# power.net
KiCad netlist of a schematic drawn in EAGLE
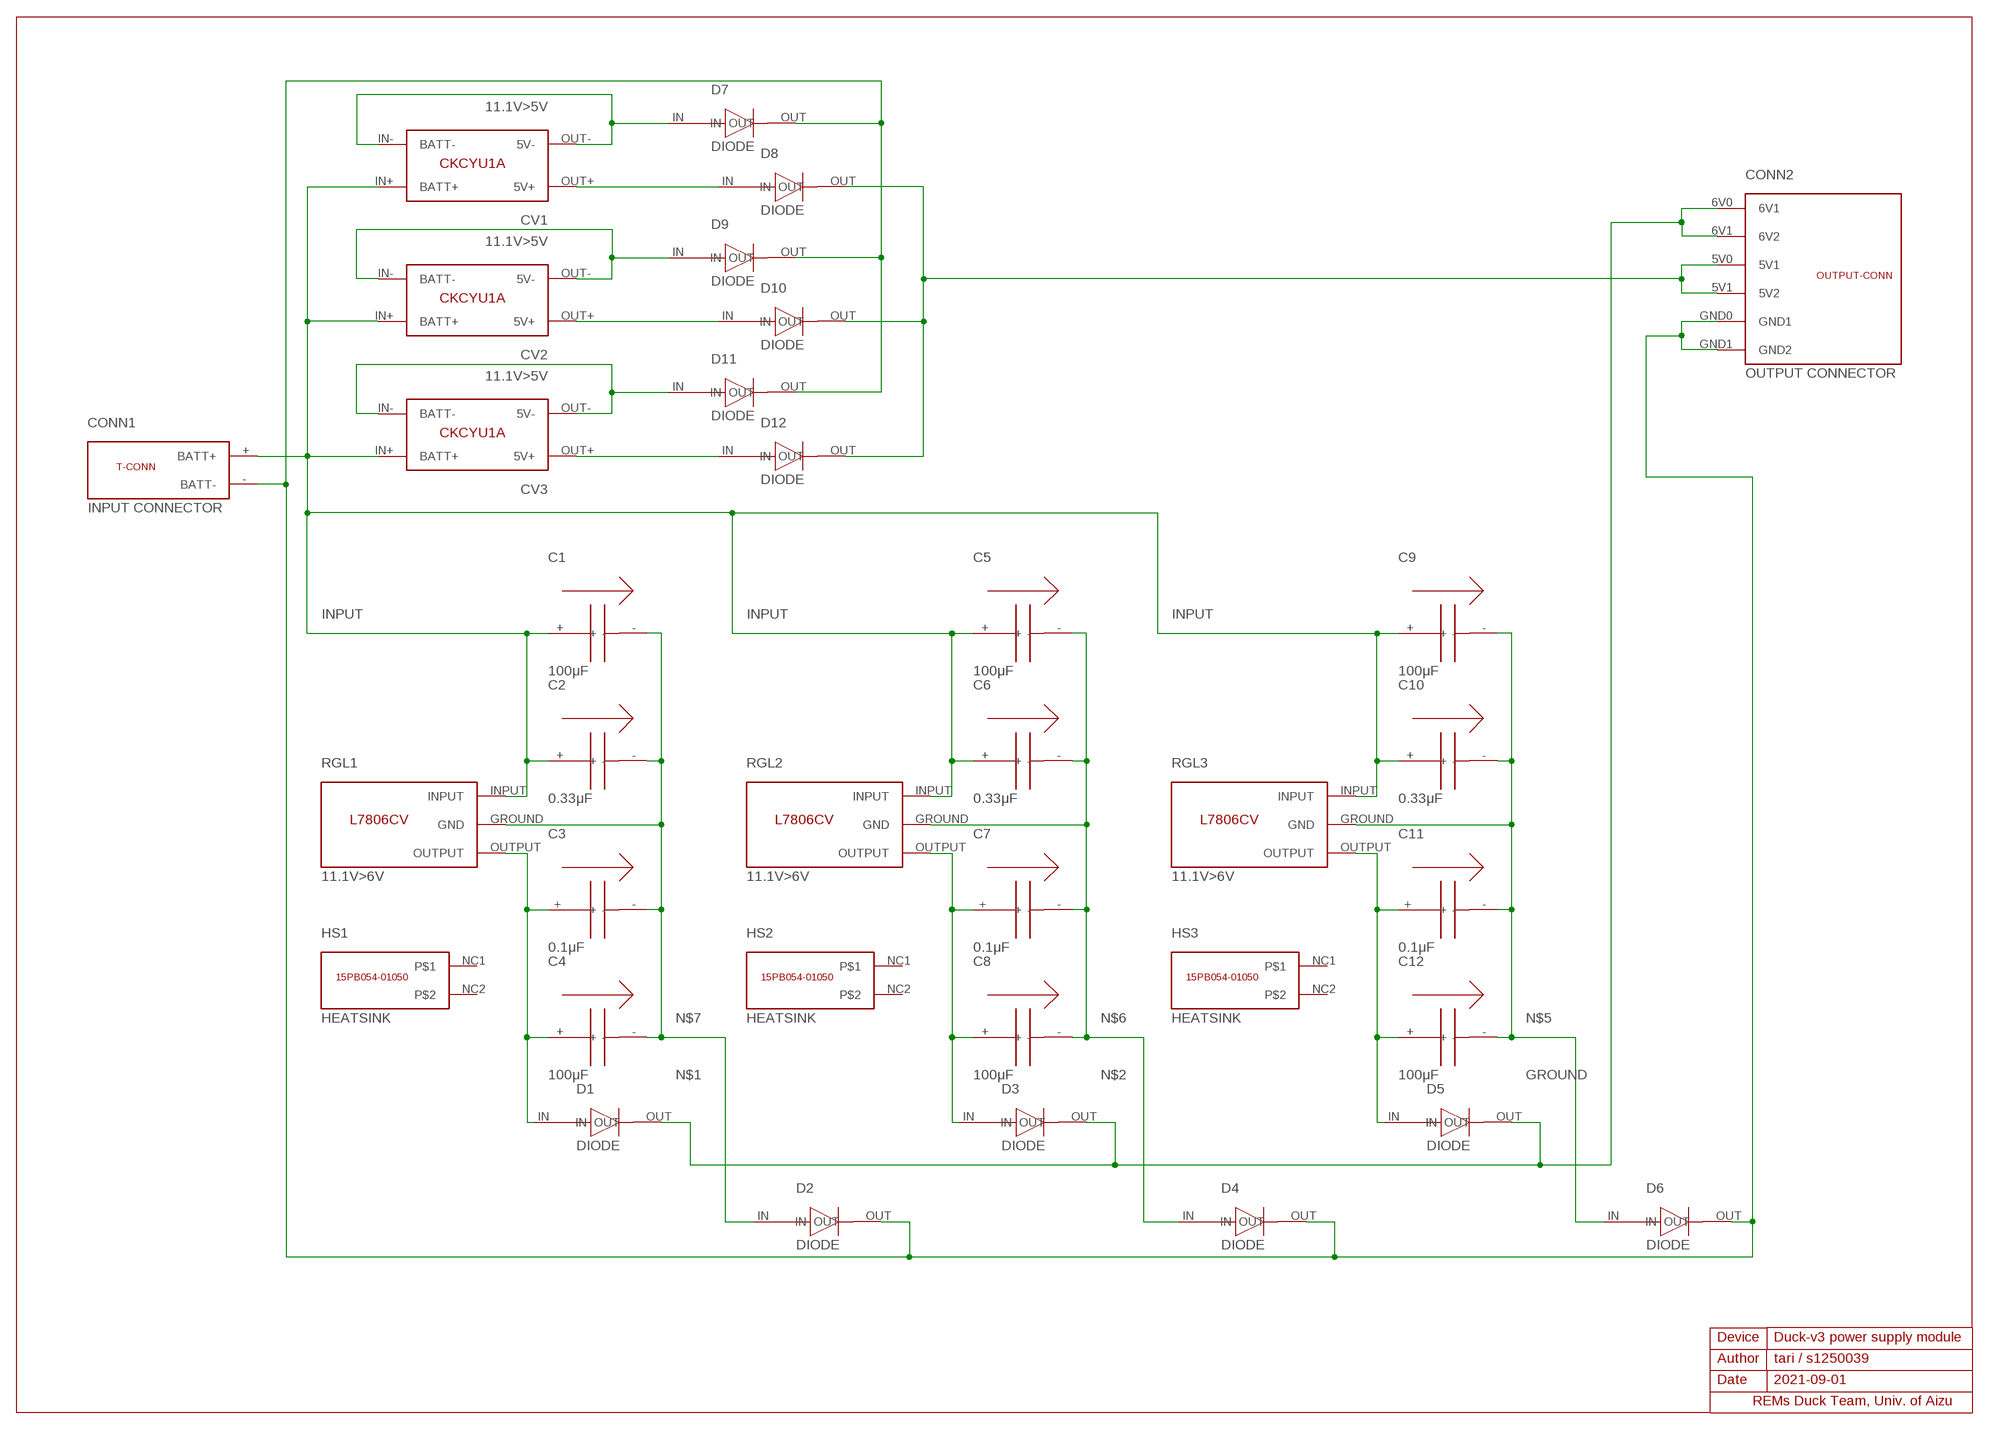
[diagram p0: schematic, sheet 1]

(export (version "E")
  (design (tool "Eeschema 10.0.6"))
  (components
    (comp (ref "C1")
      (value "100μF")
      (footprint "eagle-import:C-100μF")
      (libsource (lib "eagle-import") (part "C-100μF"))
    )
    (comp (ref "C2")
      (value "0.33μF")
      (footprint "eagle-import:C-0.33μF")
      (libsource (lib "eagle-import") (part "C-0.33μF"))
    )
    (comp (ref "C3")
      (value "0.1μF")
      (footprint "eagle-import:C-0.1μF")
      (libsource (lib "eagle-import") (part "C-0.1μF"))
    )
    (comp (ref "C4")
      (value "100μF")
      (footprint "eagle-import:C-100μF")
      (libsource (lib "eagle-import") (part "C-100μF"))
    )
    (comp (ref "C5")
      (value "100μF")
      (footprint "eagle-import:C-100μF")
      (libsource (lib "eagle-import") (part "C-100μF"))
    )
    (comp (ref "C6")
      (value "0.33μF")
      (footprint "eagle-import:C-0.33μF")
      (libsource (lib "eagle-import") (part "C-0.33μF"))
    )
    (comp (ref "C7")
      (value "0.1μF")
      (footprint "eagle-import:C-0.1μF")
      (libsource (lib "eagle-import") (part "C-0.1μF"))
    )
    (comp (ref "C8")
      (value "100μF")
      (footprint "eagle-import:C-100μF")
      (libsource (lib "eagle-import") (part "C-100μF"))
    )
    (comp (ref "C9")
      (value "100μF")
      (footprint "eagle-import:C-100μF")
      (libsource (lib "eagle-import") (part "C-100μF"))
    )
    (comp (ref "C10")
      (value "0.33μF")
      (footprint "eagle-import:C-0.33μF")
      (libsource (lib "eagle-import") (part "C-0.33μF"))
    )
    (comp (ref "C11")
      (value "0.1μF")
      (footprint "eagle-import:C-0.1μF")
      (libsource (lib "eagle-import") (part "C-0.1μF"))
    )
    (comp (ref "C12")
      (value "100μF")
      (footprint "eagle-import:C-100μF")
      (libsource (lib "eagle-import") (part "C-100μF"))
    )
    (comp (ref "CONN1")
      (value "INPUT CONNECTOR")
      (footprint "eagle-import:T-CONN")
      (libsource (lib "eagle-import") (part "T-CONN"))
    )
    (comp (ref "CONN2")
      (value "OUTPUT CONNECTOR")
      (footprint "eagle-import:OUTPUT-CONN")
      (libsource (lib "eagle-import") (part "OUTPUT-CONN"))
    )
    (comp (ref "CV1")
      (value "11.1V>5V")
      (footprint "eagle-import:CKCYU1A")
      (libsource (lib "eagle-import") (part "CKCYU1A"))
    )
    (comp (ref "CV2")
      (value "11.1V>5V")
      (footprint "eagle-import:CKCYU1A")
      (libsource (lib "eagle-import") (part "CKCYU1A"))
    )
    (comp (ref "CV3")
      (value "11.1V>5V")
      (footprint "eagle-import:CKCYU1A")
      (libsource (lib "eagle-import") (part "CKCYU1A"))
    )
    (comp (ref "D1")
      (value "DIODE")
      (footprint "eagle-import:DIODE")
      (libsource (lib "eagle-import") (part "DIODE"))
    )
    (comp (ref "D2")
      (value "DIODE")
      (footprint "eagle-import:DIODE")
      (libsource (lib "eagle-import") (part "DIODE"))
    )
    (comp (ref "D3")
      (value "DIODE")
      (footprint "eagle-import:DIODE")
      (libsource (lib "eagle-import") (part "DIODE"))
    )
    (comp (ref "D4")
      (value "DIODE")
      (footprint "eagle-import:DIODE")
      (libsource (lib "eagle-import") (part "DIODE"))
    )
    (comp (ref "D5")
      (value "DIODE")
      (footprint "eagle-import:DIODE")
      (libsource (lib "eagle-import") (part "DIODE"))
    )
    (comp (ref "D6")
      (value "DIODE")
      (footprint "eagle-import:DIODE")
      (libsource (lib "eagle-import") (part "DIODE"))
    )
    (comp (ref "D7")
      (value "DIODE")
      (footprint "eagle-import:DIODE")
      (libsource (lib "eagle-import") (part "DIODE"))
    )
    (comp (ref "D8")
      (value "DIODE")
      (footprint "eagle-import:DIODE")
      (libsource (lib "eagle-import") (part "DIODE"))
    )
    (comp (ref "D9")
      (value "DIODE")
      (footprint "eagle-import:DIODE")
      (libsource (lib "eagle-import") (part "DIODE"))
    )
    (comp (ref "D10")
      (value "DIODE")
      (footprint "eagle-import:DIODE")
      (libsource (lib "eagle-import") (part "DIODE"))
    )
    (comp (ref "D11")
      (value "DIODE")
      (footprint "eagle-import:DIODE")
      (libsource (lib "eagle-import") (part "DIODE"))
    )
    (comp (ref "D12")
      (value "DIODE")
      (footprint "eagle-import:DIODE")
      (libsource (lib "eagle-import") (part "DIODE"))
    )
    (comp (ref "HS1")
      (value "HEATSINK")
      (footprint "eagle-import:15PB054-01050")
      (libsource (lib "eagle-import") (part "15PB054-01050"))
    )
    (comp (ref "HS2")
      (value "HEATSINK")
      (footprint "eagle-import:15PB054-01050")
      (libsource (lib "eagle-import") (part "15PB054-01050"))
    )
    (comp (ref "HS3")
      (value "HEATSINK")
      (footprint "eagle-import:15PB054-01050")
      (libsource (lib "eagle-import") (part "15PB054-01050"))
    )
    (comp (ref "RGL1")
      (value "11.1V>6V")
      (footprint "eagle-import:L7806CV")
      (libsource (lib "eagle-import") (part "L7806CV"))
    )
    (comp (ref "RGL2")
      (value "11.1V>6V")
      (footprint "eagle-import:L7806CV")
      (libsource (lib "eagle-import") (part "L7806CV"))
    )
    (comp (ref "RGL3")
      (value "11.1V>6V")
      (footprint "eagle-import:L7806CV")
      (libsource (lib "eagle-import") (part "L7806CV"))
    )
  )
  (nets
    (net (code "1") (name "/GROUND") (class "Default")
      (node (ref "CONN1") (pin "-") (pinfunction "BATT-_-") (pintype "bidirectional"))
      (node (ref "CONN2") (pin "GND0") (pinfunction "GND1_GND0") (pintype "input"))
      (node (ref "CONN2") (pin "GND1") (pinfunction "GND2_GND1") (pintype "input"))
      (node (ref "D11") (pin "OUT") (pinfunction "OUT_OUT") (pintype "output"))
      (node (ref "D2") (pin "OUT") (pinfunction "OUT_OUT") (pintype "output"))
      (node (ref "D4") (pin "OUT") (pinfunction "OUT_OUT") (pintype "output"))
      (node (ref "D6") (pin "OUT") (pinfunction "OUT_OUT") (pintype "output"))
      (node (ref "D7") (pin "OUT") (pinfunction "OUT_OUT") (pintype "output"))
      (node (ref "D9") (pin "OUT") (pinfunction "OUT_OUT") (pintype "output"))
    )
    (net (code "2") (name "/INPUT") (class "Default")
      (node (ref "C1") (pin "+") (pinfunction "+_+") (pintype "input"))
      (node (ref "C10") (pin "+") (pinfunction "+_+") (pintype "input"))
      (node (ref "C2") (pin "+") (pinfunction "+_+") (pintype "input"))
      (node (ref "C5") (pin "+") (pinfunction "+_+") (pintype "input"))
      (node (ref "C6") (pin "+") (pinfunction "+_+") (pintype "input"))
      (node (ref "C9") (pin "+") (pinfunction "+_+") (pintype "input"))
      (node (ref "CONN1") (pin "+") (pinfunction "BATT+_+") (pintype "bidirectional"))
      (node (ref "CV1") (pin "IN+") (pinfunction "BATT+_IN+") (pintype "input"))
      (node (ref "CV2") (pin "IN+") (pinfunction "BATT+_IN+") (pintype "input"))
      (node (ref "CV3") (pin "IN+") (pinfunction "BATT+_IN+") (pintype "input"))
      (node (ref "RGL1") (pin "INPUT") (pinfunction "INPUT_INPUT") (pintype "input"))
      (node (ref "RGL2") (pin "INPUT") (pinfunction "INPUT_INPUT") (pintype "input"))
      (node (ref "RGL3") (pin "INPUT") (pinfunction "INPUT_INPUT") (pintype "input"))
    )
    (net (code "3") (name "/N$1") (class "Default")
      (node (ref "C3") (pin "＋") (pinfunction "+_＋") (pintype "input"))
      (node (ref "C4") (pin "+") (pinfunction "+_+") (pintype "input"))
      (node (ref "D1") (pin "IN") (pinfunction "IN_IN") (pintype "input"))
      (node (ref "RGL1") (pin "OUTPUT") (pinfunction "OUTPUT_OUTPUT") (pintype "output"))
    )
    (net (code "4") (name "/N$2") (class "Default")
      (node (ref "C7") (pin "＋") (pinfunction "+_＋") (pintype "input"))
      (node (ref "C8") (pin "+") (pinfunction "+_+") (pintype "input"))
      (node (ref "D3") (pin "IN") (pinfunction "IN_IN") (pintype "input"))
      (node (ref "RGL2") (pin "OUTPUT") (pinfunction "OUTPUT_OUTPUT") (pintype "output"))
    )
    (net (code "5") (name "/N$5") (class "Default")
      (node (ref "C10") (pin "-") (pinfunction "-_-") (pintype "output"))
      (node (ref "C11") (pin "-") (pinfunction "-_-") (pintype "output"))
      (node (ref "C12") (pin "-") (pinfunction "-_-") (pintype "output"))
      (node (ref "C9") (pin "-") (pinfunction "-_-") (pintype "output"))
      (node (ref "D6") (pin "IN") (pinfunction "IN_IN") (pintype "input"))
      (node (ref "RGL3") (pin "GROUND") (pinfunction "GND_GROUND") (pintype "output"))
    )
    (net (code "6") (name "/N$6") (class "Default")
      (node (ref "C5") (pin "-") (pinfunction "-_-") (pintype "output"))
      (node (ref "C6") (pin "-") (pinfunction "-_-") (pintype "output"))
      (node (ref "C7") (pin "-") (pinfunction "-_-") (pintype "output"))
      (node (ref "C8") (pin "-") (pinfunction "-_-") (pintype "output"))
      (node (ref "D4") (pin "IN") (pinfunction "IN_IN") (pintype "input"))
      (node (ref "RGL2") (pin "GROUND") (pinfunction "GND_GROUND") (pintype "output"))
    )
    (net (code "7") (name "/N$7") (class "Default")
      (node (ref "C1") (pin "-") (pinfunction "-_-") (pintype "output"))
      (node (ref "C2") (pin "-") (pinfunction "-_-") (pintype "output"))
      (node (ref "C3") (pin "-") (pinfunction "-_-") (pintype "output"))
      (node (ref "C4") (pin "-") (pinfunction "-_-") (pintype "output"))
      (node (ref "D2") (pin "IN") (pinfunction "IN_IN") (pintype "input"))
      (node (ref "RGL1") (pin "GROUND") (pinfunction "GND_GROUND") (pintype "output"))
    )
    (net (code "8") (name "Net-(C11-+)") (class "Default")
      (node (ref "C11") (pin "＋") (pinfunction "+_＋") (pintype "input"))
      (node (ref "C12") (pin "+") (pinfunction "+_+") (pintype "input"))
      (node (ref "D5") (pin "IN") (pinfunction "IN_IN") (pintype "input"))
      (node (ref "RGL3") (pin "OUTPUT") (pinfunction "OUTPUT_OUTPUT") (pintype "output"))
    )
    (net (code "9") (name "Net-(CONN2-5V1)") (class "Default")
      (node (ref "CONN2") (pin "5V0") (pinfunction "5V1_5V0") (pintype "input"))
      (node (ref "CONN2") (pin "5V1") (pinfunction "5V2_5V1") (pintype "input"))
      (node (ref "D10") (pin "OUT") (pinfunction "OUT_OUT") (pintype "output"))
      (node (ref "D12") (pin "OUT") (pinfunction "OUT_OUT") (pintype "output"))
      (node (ref "D8") (pin "OUT") (pinfunction "OUT_OUT") (pintype "output"))
    )
    (net (code "10") (name "Net-(CONN2-6V1)") (class "Default")
      (node (ref "CONN2") (pin "6V0") (pinfunction "6V1_6V0") (pintype "input"))
      (node (ref "CONN2") (pin "6V1") (pinfunction "6V2_6V1") (pintype "input"))
      (node (ref "D1") (pin "OUT") (pinfunction "OUT_OUT") (pintype "output"))
      (node (ref "D3") (pin "OUT") (pinfunction "OUT_OUT") (pintype "output"))
      (node (ref "D5") (pin "OUT") (pinfunction "OUT_OUT") (pintype "output"))
    )
    (net (code "11") (name "Net-(CV1-5V+)") (class "Default")
      (node (ref "CV1") (pin "OUT+") (pinfunction "5V+_OUT+") (pintype "output"))
      (node (ref "D8") (pin "IN") (pinfunction "IN_IN") (pintype "input"))
    )
    (net (code "12") (name "Net-(CV1-5V-)") (class "Default")
      (node (ref "CV1") (pin "IN-") (pinfunction "BATT-_IN-") (pintype "input"))
      (node (ref "CV1") (pin "OUT-") (pinfunction "5V-_OUT-") (pintype "output"))
      (node (ref "D7") (pin "IN") (pinfunction "IN_IN") (pintype "input"))
    )
    (net (code "13") (name "Net-(CV2-5V+)") (class "Default")
      (node (ref "CV2") (pin "OUT+") (pinfunction "5V+_OUT+") (pintype "output"))
      (node (ref "D10") (pin "IN") (pinfunction "IN_IN") (pintype "input"))
    )
    (net (code "14") (name "Net-(CV2-5V-)") (class "Default")
      (node (ref "CV2") (pin "IN-") (pinfunction "BATT-_IN-") (pintype "input"))
      (node (ref "CV2") (pin "OUT-") (pinfunction "5V-_OUT-") (pintype "output"))
      (node (ref "D9") (pin "IN") (pinfunction "IN_IN") (pintype "input"))
    )
    (net (code "15") (name "Net-(CV3-5V+)") (class "Default")
      (node (ref "CV3") (pin "OUT+") (pinfunction "5V+_OUT+") (pintype "output"))
      (node (ref "D12") (pin "IN") (pinfunction "IN_IN") (pintype "input"))
    )
    (net (code "16") (name "Net-(CV3-5V-)") (class "Default")
      (node (ref "CV3") (pin "IN-") (pinfunction "BATT-_IN-") (pintype "input"))
      (node (ref "CV3") (pin "OUT-") (pinfunction "5V-_OUT-") (pintype "output"))
      (node (ref "D11") (pin "IN") (pinfunction "IN_IN") (pintype "input"))
    )
    (net (code "17") (name "unconnected-(HS1-P$1-PadNC1)") (class "Default")
      (node (ref "HS1") (pin "NC1") (pinfunction "P$1_NC1") (pintype "no_connect"))
    )
    (net (code "18") (name "unconnected-(HS1-P$2-PadNC2)") (class "Default")
      (node (ref "HS1") (pin "NC2") (pinfunction "P$2_NC2") (pintype "no_connect"))
    )
    (net (code "19") (name "unconnected-(HS2-P$1-PadNC1)") (class "Default")
      (node (ref "HS2") (pin "NC1") (pinfunction "P$1_NC1") (pintype "no_connect"))
    )
    (net (code "20") (name "unconnected-(HS2-P$2-PadNC2)") (class "Default")
      (node (ref "HS2") (pin "NC2") (pinfunction "P$2_NC2") (pintype "no_connect"))
    )
    (net (code "21") (name "unconnected-(HS3-P$1-PadNC1)") (class "Default")
      (node (ref "HS3") (pin "NC1") (pinfunction "P$1_NC1") (pintype "no_connect"))
    )
    (net (code "22") (name "unconnected-(HS3-P$2-PadNC2)") (class "Default")
      (node (ref "HS3") (pin "NC2") (pinfunction "P$2_NC2") (pintype "no_connect"))
    )
  )
)
